# module_flags_reg.net
KiCad netlist of a schematic drawn in EAGLE
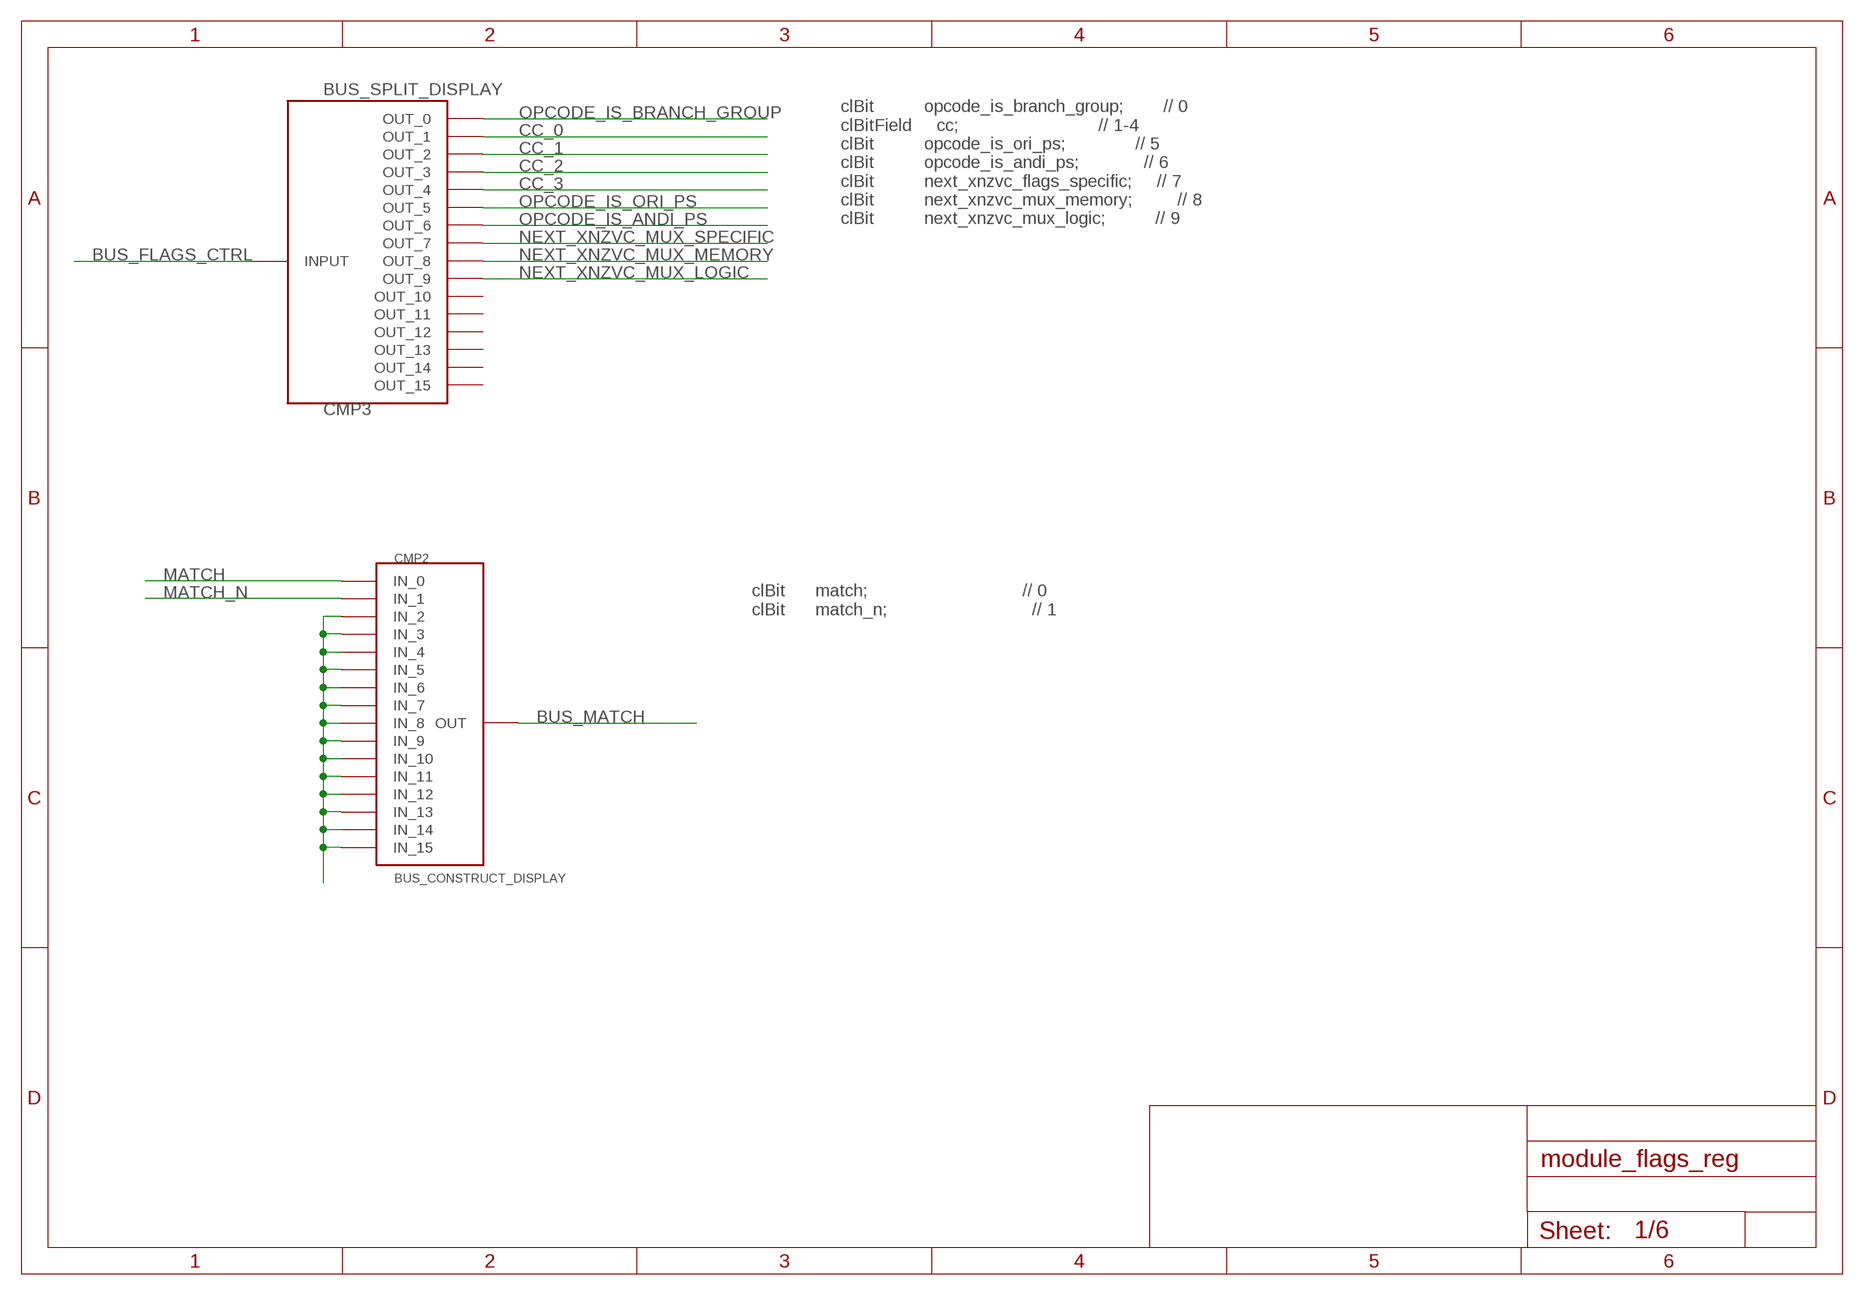
[diagram p0: schematic, sheet 1]
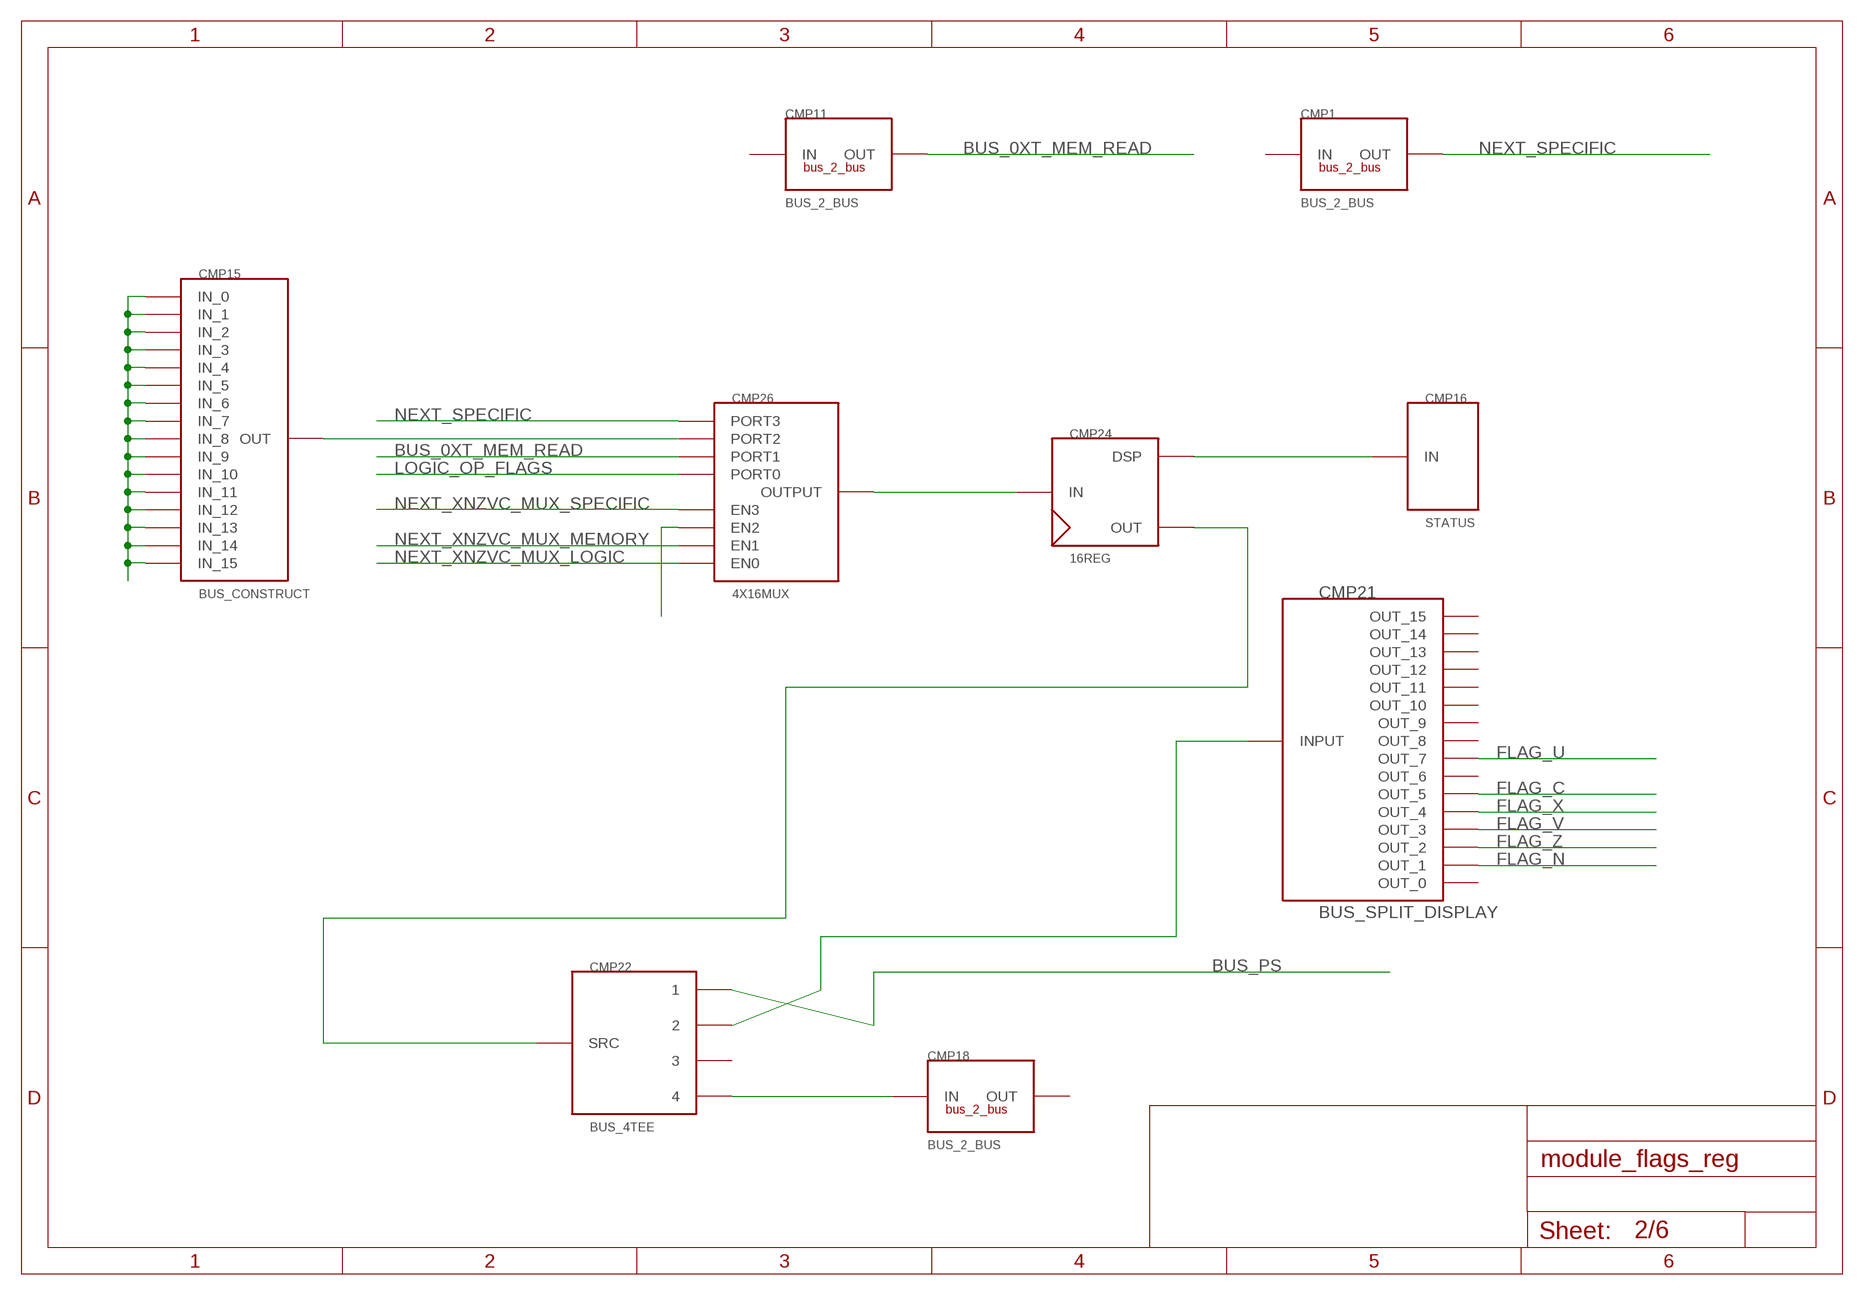
[diagram p1: schematic, sheet 2]
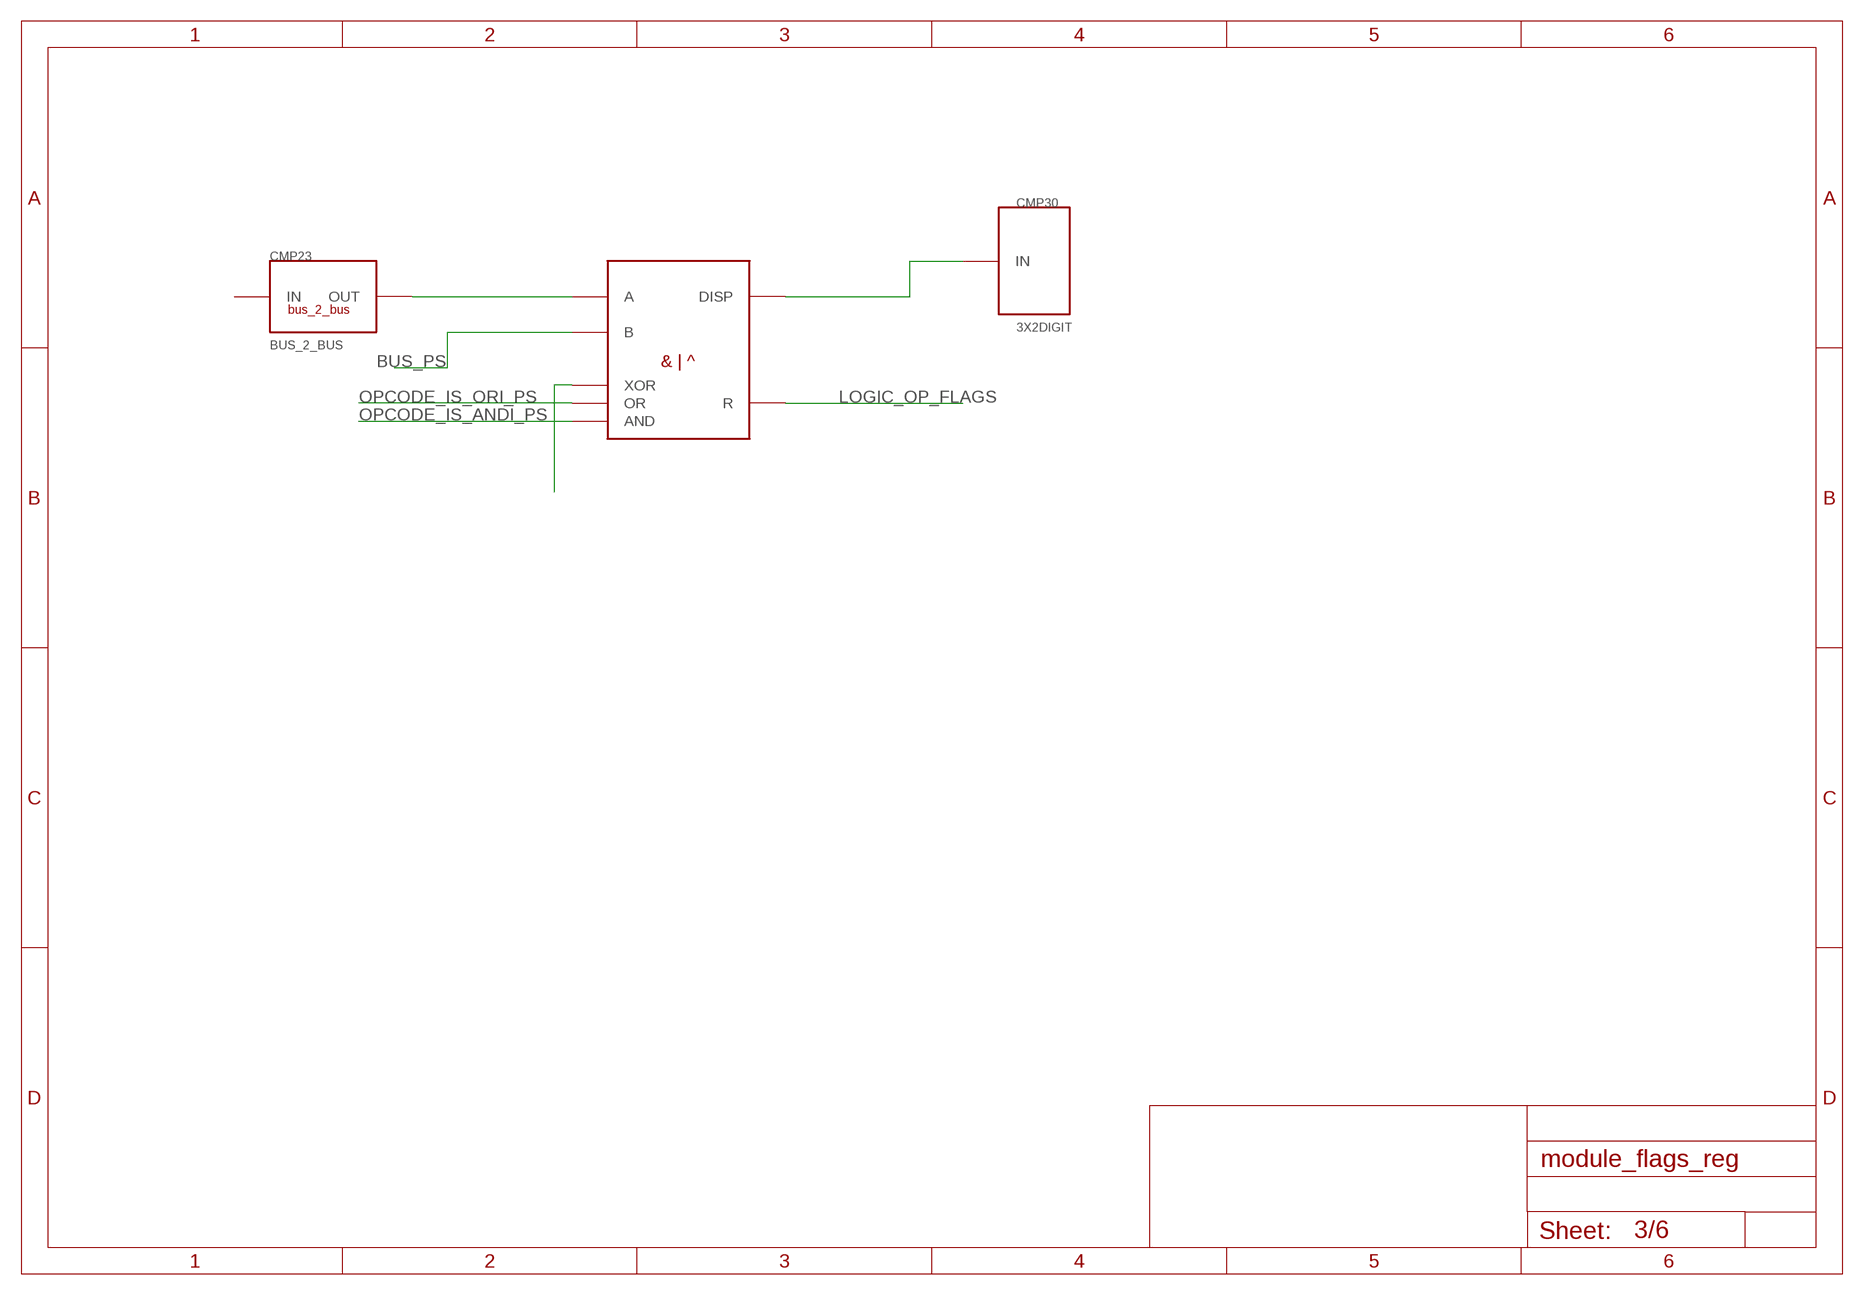
[diagram p2: schematic, sheet 3]
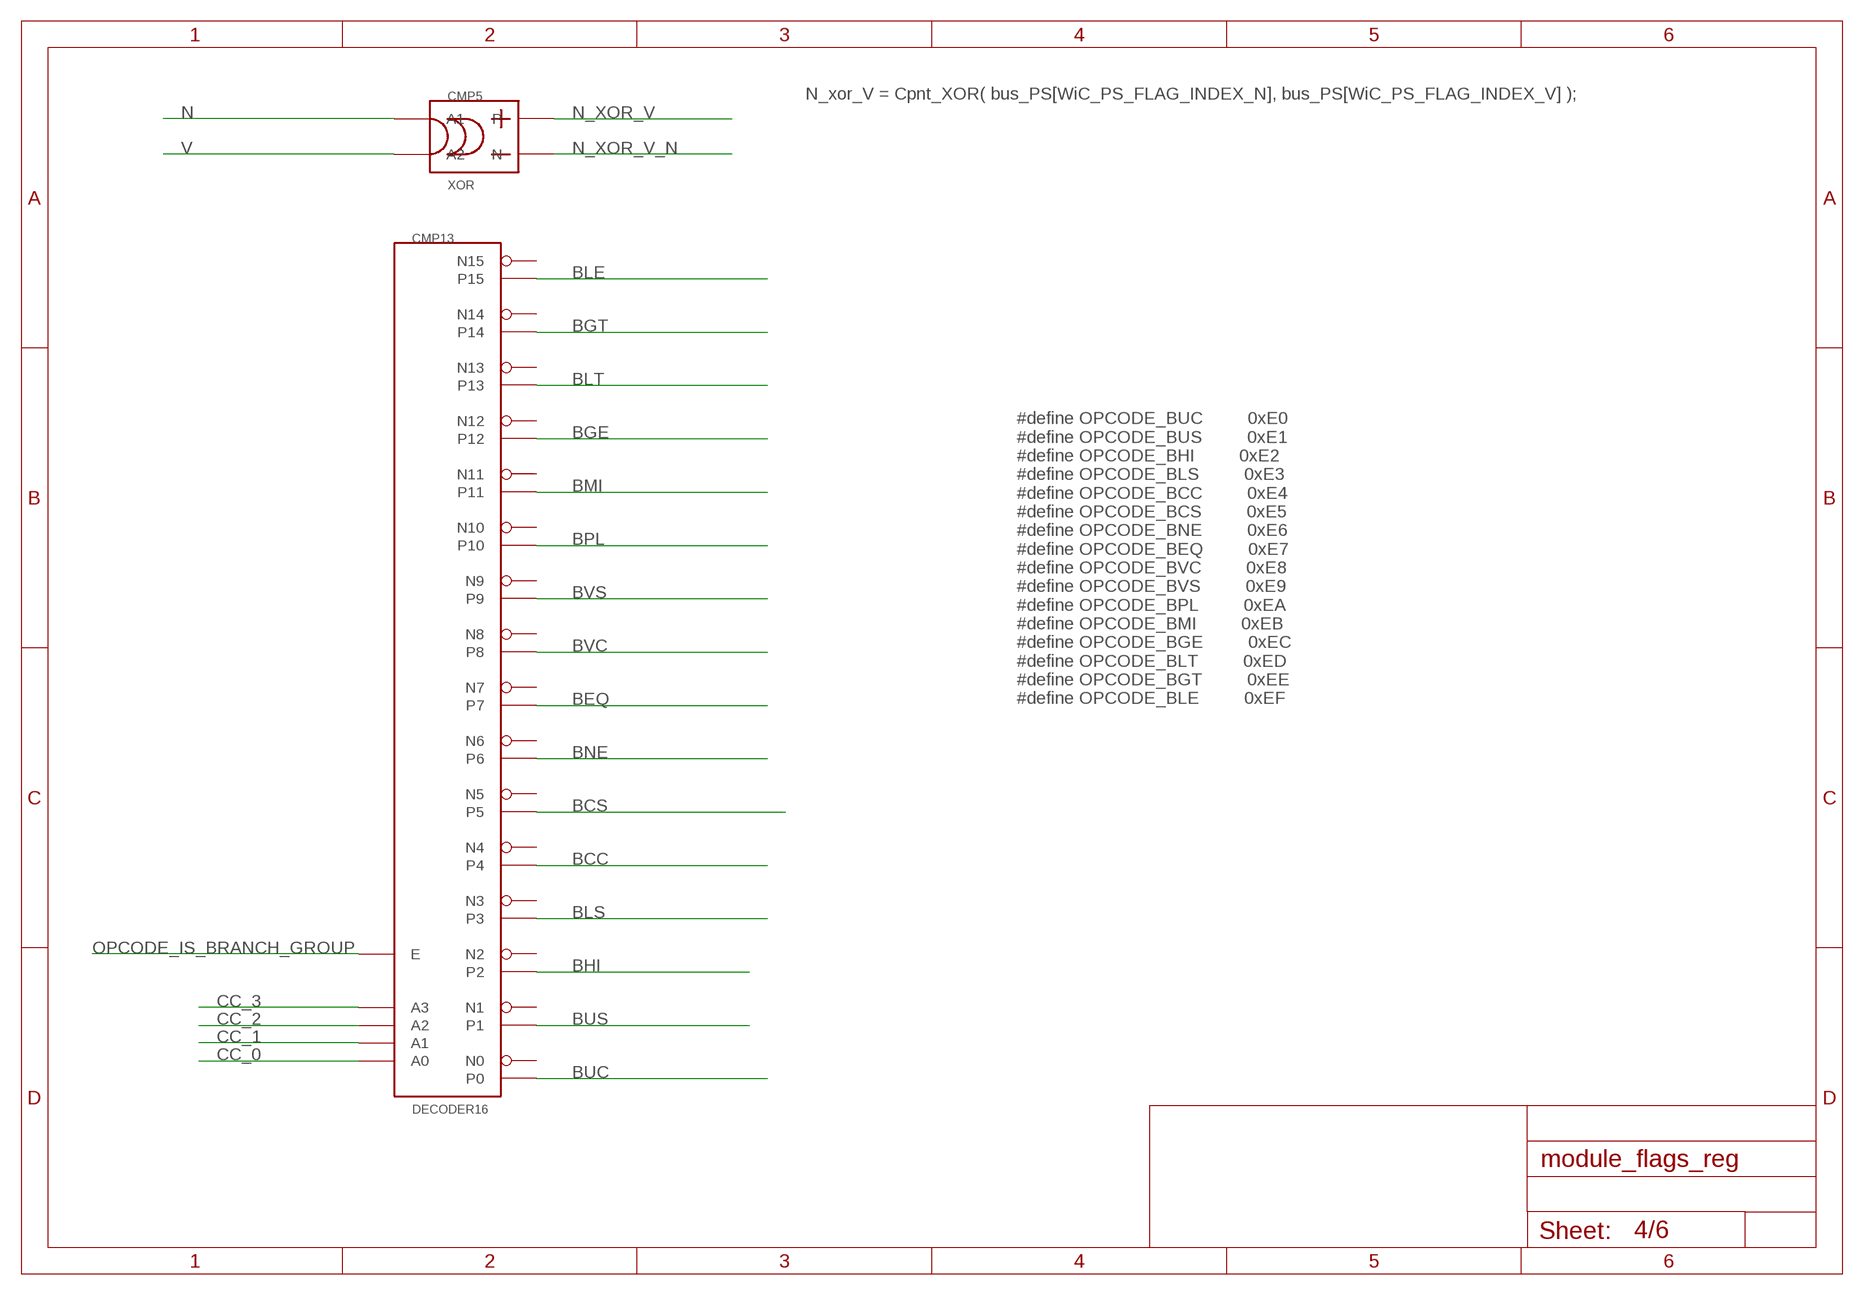
[diagram p3: schematic, sheet 4]
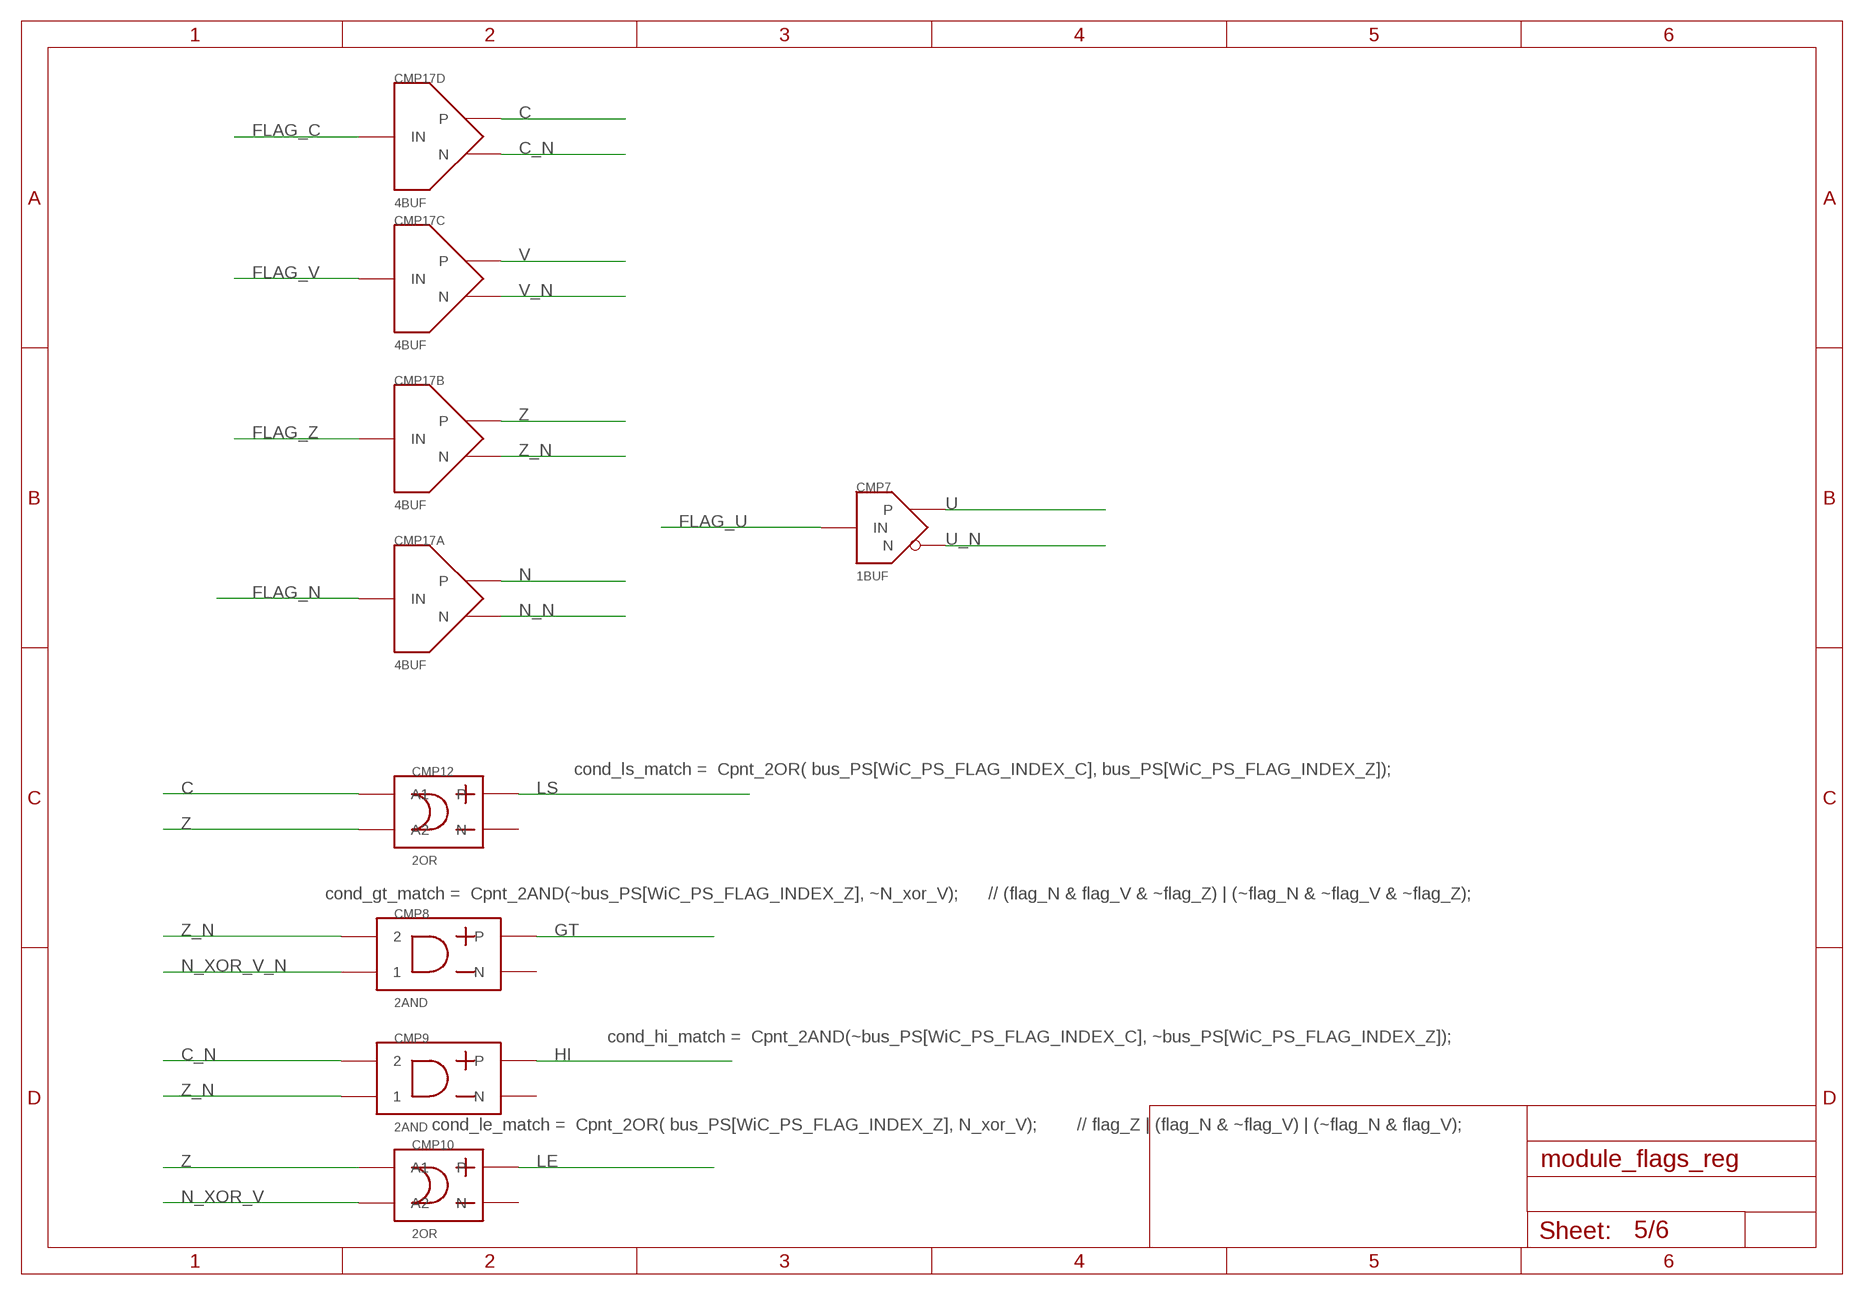
[diagram p4: schematic, sheet 5]
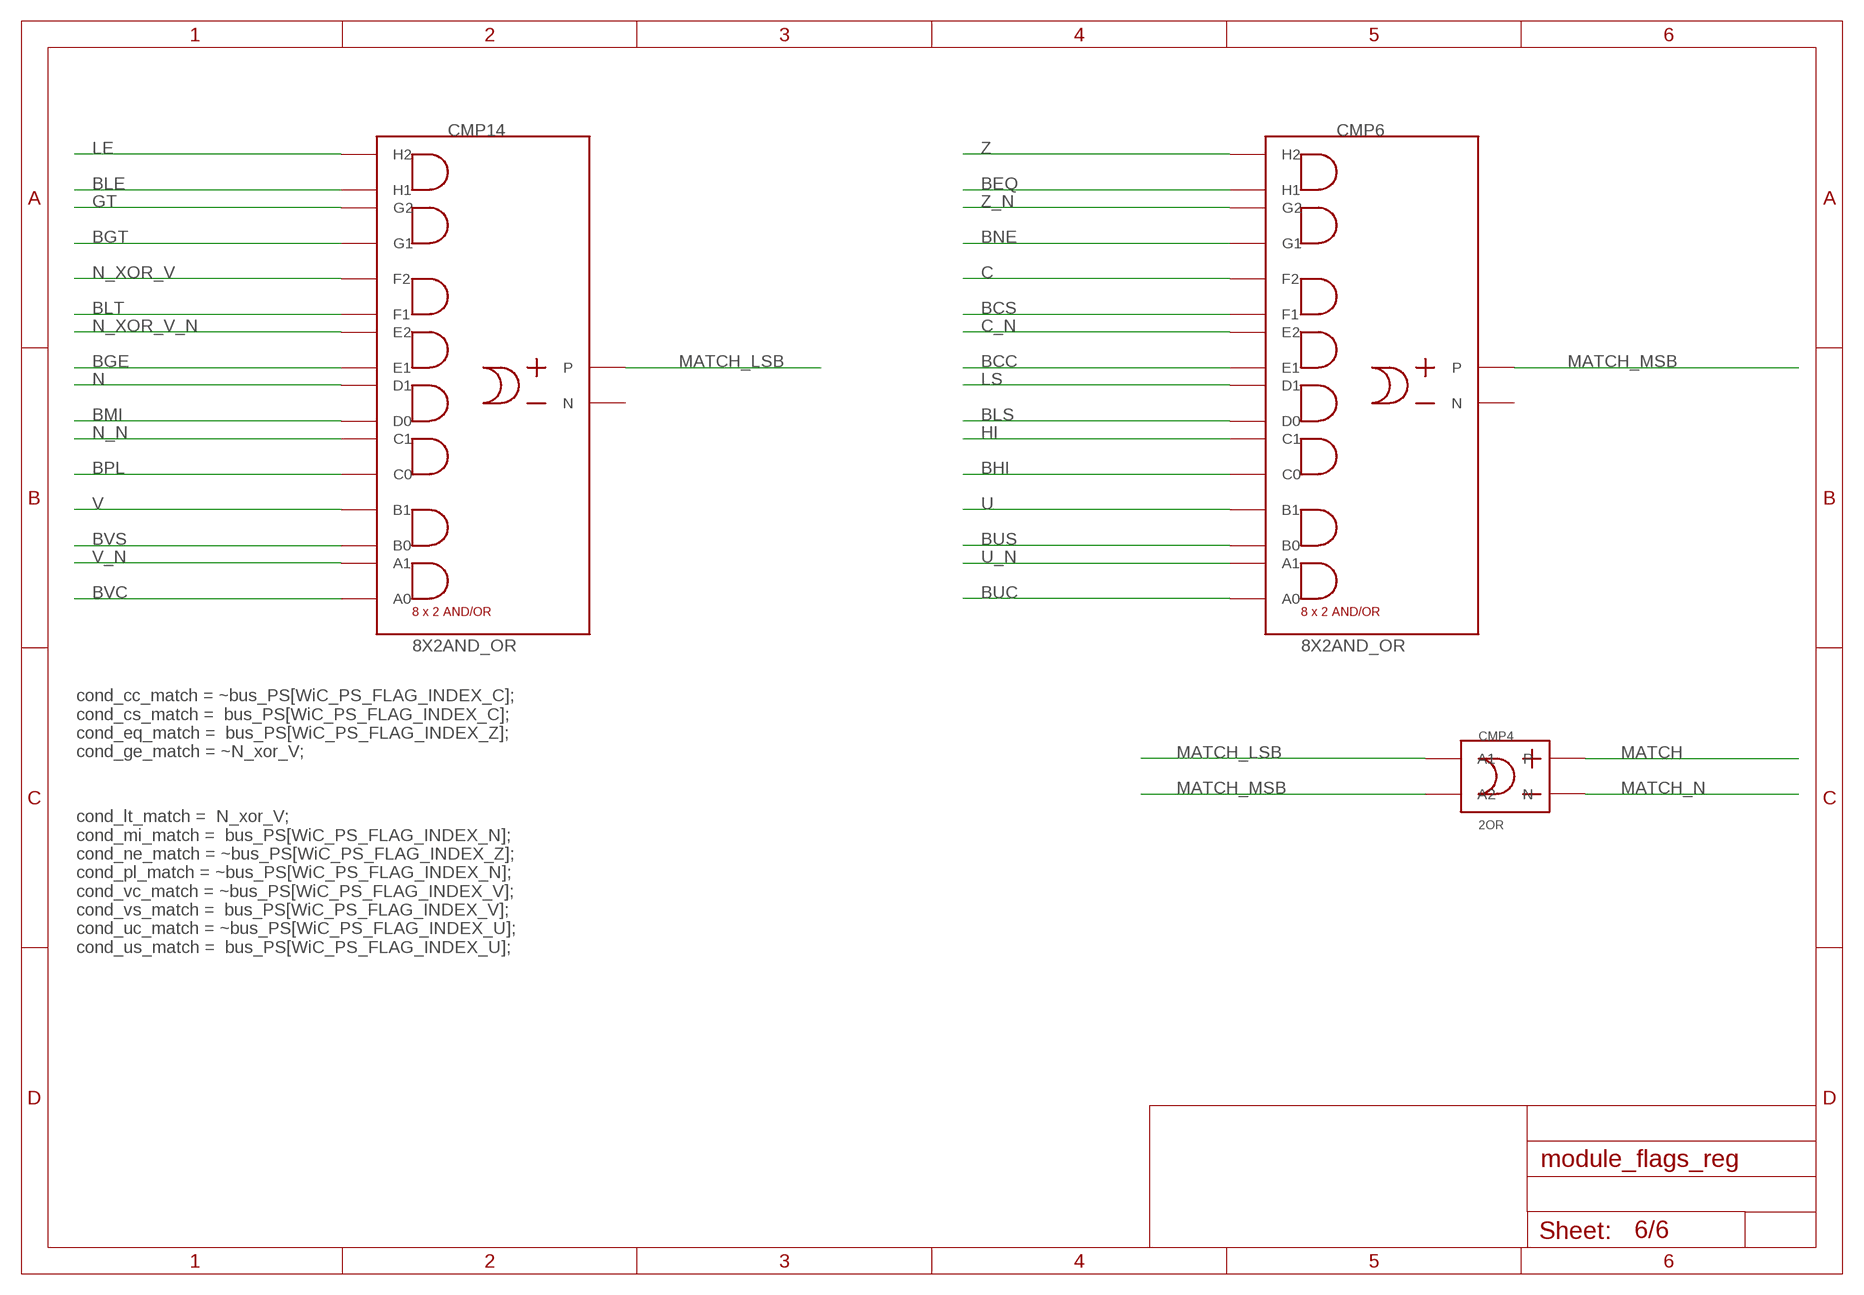
[diagram p5: schematic, sheet 6]

(export (version "E")
  (design (tool "Eeschema 10.0.6"))
  (components
    (comp (ref "CMP1")
      (value "BUS_2_BUS")
      (footprint "eagle-import:BUS2BUS")
      (libsource (lib "eagle-import") (part "BUS_2_BUS"))
    )
    (comp (ref "CMP11")
      (value "BUS_2_BUS")
      (footprint "eagle-import:BUS2BUS")
      (libsource (lib "eagle-import") (part "BUS_2_BUS"))
    )
    (comp (ref "CMP15")
      (value "BUS_CONSTRUCT")
      (footprint "eagle-import:BUS_SPLIT")
      (libsource (lib "eagle-import") (part "BUS_CONSTRUCT"))
    )
    (comp (ref "CMP16")
      (value "STATUS")
      (footprint "eagle-import:STATUS")
      (libsource (lib "eagle-import") (part "STATUS"))
    )
    (comp (ref "CMP18")
      (value "BUS_2_BUS")
      (footprint "eagle-import:BUS2BUS")
      (libsource (lib "eagle-import") (part "BUS_2_BUS"))
    )
    (comp (ref "CMP21")
      (value "BUS_SPLIT_DISPLAY")
      (footprint "eagle-import:BUS_SPLIT_DISPLAY")
      (libsource (lib "eagle-import") (part "BUS_SPLIT_DISPLAY"))
    )
    (comp (ref "CMP22")
      (value "BUS_4TEE")
      (footprint "eagle-import:BUS_4TEE")
      (libsource (lib "eagle-import") (part "BUS_4TEE"))
    )
    (comp (ref "CMP24")
      (value "16REG")
      (footprint "eagle-import:16REG")
      (libsource (lib "eagle-import") (part "16REG"))
    )
    (comp (ref "CMP26")
      (value "4X16MUX")
      (footprint "eagle-import:4X16MUX")
      (libsource (lib "eagle-import") (part "4X16MUX"))
    )
    (comp (ref "CMP4")
      (value "2OR")
      (footprint "eagle-import:2OR")
      (libsource (lib "eagle-import") (part "2OR"))
    )
    (comp (ref "CMP6")
      (value "8X2AND_OR")
      (footprint "eagle-import:8X2AND_OR")
      (libsource (lib "eagle-import") (part "8X2AND_OR"))
    )
    (comp (ref "CMP14")
      (value "8X2AND_OR")
      (footprint "eagle-import:8X2AND_OR")
      (libsource (lib "eagle-import") (part "8X2AND_OR"))
    )
    (comp (ref "CMP2")
      (value "BUS_CONSTRUCT_DISPLAY")
      (footprint "eagle-import:BUS_SPLIT_DISPLAY")
      (libsource (lib "eagle-import") (part "BUS_CONSTRUCT_DISPLAY"))
    )
    (comp (ref "CMP3")
      (value "BUS_SPLIT_DISPLAY")
      (footprint "eagle-import:BUS_SPLIT_DISPLAY")
      (libsource (lib "eagle-import") (part "BUS_SPLIT_DISPLAY"))
    )
    (comp (ref "CMP23")
      (value "BUS_2_BUS")
      (footprint "eagle-import:BUS2BUS")
      (libsource (lib "eagle-import") (part "BUS_2_BUS"))
    )
    (comp (ref "CMP28")
      (value "8BIT_LOGIC")
      (footprint "eagle-import:8BIT_LOGIC")
      (libsource (lib "eagle-import") (part "8BIT_LOGIC"))
    )
    (comp (ref "CMP30")
      (value "3X2DIGIT")
      (footprint "eagle-import:3X2DIGIT")
      (libsource (lib "eagle-import") (part "3X2DIGIT"))
    )
    (comp (ref "CMP7")
      (value "1BUF")
      (footprint "eagle-import:1BUF")
      (libsource (lib "eagle-import") (part "1BUF"))
    )
    (comp (ref "CMP8")
      (value "2AND")
      (footprint "eagle-import:2AND")
      (libsource (lib "eagle-import") (part "2AND"))
    )
    (comp (ref "CMP9")
      (value "2AND")
      (footprint "eagle-import:2AND")
      (libsource (lib "eagle-import") (part "2AND"))
    )
    (comp (ref "CMP10")
      (value "2OR")
      (footprint "eagle-import:2OR")
      (libsource (lib "eagle-import") (part "2OR"))
    )
    (comp (ref "CMP12")
      (value "2OR")
      (footprint "eagle-import:2OR")
      (libsource (lib "eagle-import") (part "2OR"))
    )
    (comp (ref "CMP17")
      (value "4BUF")
      (footprint "eagle-import:4BUF")
      (libsource (lib "eagle-import") (part "4BUF"))
    )
    (comp (ref "CMP5")
      (value "XOR")
      (footprint "eagle-import:XOR")
      (libsource (lib "eagle-import") (part "XOR"))
    )
    (comp (ref "CMP13")
      (value "DECODER16")
      (footprint "eagle-import:DECODER16")
      (libsource (lib "eagle-import") (part "DECODER16"))
    )
  )
  (nets
    (net (code "1") (name "BCC") (class "Default")
      (node (ref "CMP13") (pin "P4") (pinfunction "P4_P4") (pintype "output"))
      (node (ref "CMP6") (pin "P$9") (pinfunction "E1_P$9") (pintype "input"))
    )
    (net (code "2") (name "BCS") (class "Default")
      (node (ref "CMP13") (pin "P5") (pinfunction "P5_P5") (pintype "output"))
      (node (ref "CMP6") (pin "P$11") (pinfunction "F1_P$11") (pintype "input"))
    )
    (net (code "3") (name "BEQ") (class "Default")
      (node (ref "CMP13") (pin "P7") (pinfunction "P7_P7") (pintype "output"))
      (node (ref "CMP6") (pin "P$15") (pinfunction "H1_P$15") (pintype "input"))
    )
    (net (code "4") (name "BGE") (class "Default")
      (node (ref "CMP13") (pin "P12") (pinfunction "P12_P12") (pintype "output"))
      (node (ref "CMP14") (pin "P$9") (pinfunction "E1_P$9") (pintype "input"))
    )
    (net (code "5") (name "BGT") (class "Default")
      (node (ref "CMP13") (pin "P14") (pinfunction "P14_P14") (pintype "output"))
      (node (ref "CMP14") (pin "P$13") (pinfunction "G1_P$13") (pintype "input"))
    )
    (net (code "6") (name "BHI") (class "Default")
      (node (ref "CMP13") (pin "P2") (pinfunction "P2_P2") (pintype "output"))
      (node (ref "CMP6") (pin "P$5") (pinfunction "C0_P$5") (pintype "input"))
    )
    (net (code "7") (name "BLE") (class "Default")
      (node (ref "CMP13") (pin "P15") (pinfunction "P15_P15") (pintype "output"))
      (node (ref "CMP14") (pin "P$15") (pinfunction "H1_P$15") (pintype "input"))
    )
    (net (code "8") (name "BLS") (class "Default")
      (node (ref "CMP13") (pin "P3") (pinfunction "P3_P3") (pintype "output"))
      (node (ref "CMP6") (pin "P$7") (pinfunction "D0_P$7") (pintype "input"))
    )
    (net (code "9") (name "BLT") (class "Default")
      (node (ref "CMP13") (pin "P13") (pinfunction "P13_P13") (pintype "output"))
      (node (ref "CMP14") (pin "P$11") (pinfunction "F1_P$11") (pintype "input"))
    )
    (net (code "10") (name "BMI") (class "Default")
      (node (ref "CMP13") (pin "P11") (pinfunction "P11_P11") (pintype "output"))
      (node (ref "CMP14") (pin "P$7") (pinfunction "D0_P$7") (pintype "input"))
    )
    (net (code "11") (name "BNE") (class "Default")
      (node (ref "CMP13") (pin "P6") (pinfunction "P6_P6") (pintype "output"))
      (node (ref "CMP6") (pin "P$13") (pinfunction "G1_P$13") (pintype "input"))
    )
    (net (code "12") (name "BPL") (class "Default")
      (node (ref "CMP13") (pin "P10") (pinfunction "P10_P10") (pintype "output"))
      (node (ref "CMP14") (pin "P$5") (pinfunction "C0_P$5") (pintype "input"))
    )
    (net (code "13") (name "BUC") (class "Default")
      (node (ref "CMP13") (pin "P0") (pinfunction "P0_P0") (pintype "output"))
      (node (ref "CMP6") (pin "P$1") (pinfunction "A0_P$1") (pintype "input"))
    )
    (net (code "14") (name "BUS") (class "Default")
      (node (ref "CMP13") (pin "P1") (pinfunction "P1_P1") (pintype "output"))
      (node (ref "CMP6") (pin "P$3") (pinfunction "B0_P$3") (pintype "input"))
    )
    (net (code "15") (name "BUS_0XT_MEM_READ") (class "Default")
      (node (ref "CMP11") (pin "P$2") (pinfunction "OUT_P$2") (pintype "output"))
      (node (ref "CMP26") (pin "PORT1") (pinfunction "PORT1_PORT1") (pintype "input"))
    )
    (net (code "16") (name "BUS_FLAGS_CTRL") (class "Default")
      (node (ref "CMP3") (pin "INPUT") (pinfunction "INPUT_INPUT") (pintype "input"))
    )
    (net (code "17") (name "BUS_MATCH") (class "Default")
      (node (ref "CMP2") (pin "INPUT") (pinfunction "OUT_INPUT") (pintype "output"))
    )
    (net (code "18") (name "BUS_PS") (class "Default")
      (node (ref "CMP22") (pin "1") (pinfunction "1_1") (pintype "output"))
      (node (ref "CMP28") (pin "B") (pinfunction "B_B") (pintype "input"))
    )
    (net (code "19") (name "BVC") (class "Default")
      (node (ref "CMP13") (pin "P8") (pinfunction "P8_P8") (pintype "output"))
      (node (ref "CMP14") (pin "P$1") (pinfunction "A0_P$1") (pintype "input"))
    )
    (net (code "20") (name "BVS") (class "Default")
      (node (ref "CMP13") (pin "P9") (pinfunction "P9_P9") (pintype "output"))
      (node (ref "CMP14") (pin "P$3") (pinfunction "B0_P$3") (pintype "input"))
    )
    (net (code "21") (name "C") (class "Default")
      (node (ref "CMP12") (pin "P$2") (pinfunction "A1_P$2") (pintype "input"))
      (node (ref "CMP17") (pin "P4") (pinfunction "P_P4") (pintype "output"))
      (node (ref "CMP6") (pin "P$12") (pinfunction "F2_P$12") (pintype "input"))
    )
    (net (code "22") (name "CC_0") (class "Default")
      (node (ref "CMP13") (pin "A0") (pinfunction "A0_A0") (pintype "input"))
      (node (ref "CMP3") (pin "P$2") (pinfunction "OUT_1_P$2") (pintype "output"))
    )
    (net (code "23") (name "CC_1") (class "Default")
      (node (ref "CMP13") (pin "A1") (pinfunction "A1_A1") (pintype "input"))
      (node (ref "CMP3") (pin "P$3") (pinfunction "OUT_2_P$3") (pintype "output"))
    )
    (net (code "24") (name "CC_2") (class "Default")
      (node (ref "CMP13") (pin "A2") (pinfunction "A2_A2") (pintype "input"))
      (node (ref "CMP3") (pin "P$4") (pinfunction "OUT_3_P$4") (pintype "output"))
    )
    (net (code "25") (name "CC_3") (class "Default")
      (node (ref "CMP13") (pin "A3") (pinfunction "A3_A3") (pintype "input"))
      (node (ref "CMP3") (pin "P$5") (pinfunction "OUT_4_P$5") (pintype "output"))
    )
    (net (code "26") (name "C_N") (class "Default")
      (node (ref "CMP17") (pin "N4") (pinfunction "N_N4") (pintype "output"))
      (node (ref "CMP6") (pin "P$10") (pinfunction "E2_P$10") (pintype "input"))
      (node (ref "CMP9") (pin "P$2") (pinfunction "2_P$2") (pintype "input"))
    )
    (net (code "27") (name "FLAG_C") (class "Default")
      (node (ref "CMP17") (pin "A4") (pinfunction "IN_A4") (pintype "input"))
      (node (ref "CMP21") (pin "P$6") (pinfunction "OUT_5_P$6") (pintype "output"))
    )
    (net (code "28") (name "FLAG_N") (class "Default")
      (node (ref "CMP17") (pin "A1") (pinfunction "IN_A1") (pintype "input"))
      (node (ref "CMP21") (pin "P$2") (pinfunction "OUT_1_P$2") (pintype "output"))
    )
    (net (code "29") (name "FLAG_U") (class "Default")
      (node (ref "CMP21") (pin "P$8") (pinfunction "OUT_7_P$8") (pintype "output"))
      (node (ref "CMP7") (pin "IN") (pinfunction "IN_IN") (pintype "input"))
    )
    (net (code "30") (name "FLAG_V") (class "Default")
      (node (ref "CMP17") (pin "A3") (pinfunction "IN_A3") (pintype "input"))
      (node (ref "CMP21") (pin "P$4") (pinfunction "OUT_3_P$4") (pintype "output"))
    )
    (net (code "31") (name "FLAG_X") (class "Default")
      (node (ref "CMP21") (pin "P$5") (pinfunction "OUT_4_P$5") (pintype "output"))
    )
    (net (code "32") (name "FLAG_Z") (class "Default")
      (node (ref "CMP17") (pin "A2") (pinfunction "IN_A2") (pintype "input"))
      (node (ref "CMP21") (pin "P$3") (pinfunction "OUT_2_P$3") (pintype "output"))
    )
    (net (code "33") (name "GT") (class "Default")
      (node (ref "CMP14") (pin "P$14") (pinfunction "G2_P$14") (pintype "input"))
      (node (ref "CMP8") (pin "OUT_P") (pinfunction "P_OUT_P") (pintype "output"))
    )
    (net (code "34") (name "HI") (class "Default")
      (node (ref "CMP6") (pin "P$6") (pinfunction "C1_P$6") (pintype "input"))
      (node (ref "CMP9") (pin "OUT_P") (pinfunction "P_OUT_P") (pintype "output"))
    )
    (net (code "35") (name "LE") (class "Default")
      (node (ref "CMP10") (pin "OUT_P") (pinfunction "P_OUT_P") (pintype "output"))
      (node (ref "CMP14") (pin "P$16") (pinfunction "H2_P$16") (pintype "input"))
    )
    (net (code "36") (name "LOGIC_OP_FLAGS") (class "Default")
      (node (ref "CMP26") (pin "PORT0") (pinfunction "PORT0_PORT0") (pintype "input"))
      (node (ref "CMP28") (pin "R") (pinfunction "R_R") (pintype "output"))
    )
    (net (code "37") (name "LS") (class "Default")
      (node (ref "CMP12") (pin "OUT_P") (pinfunction "P_OUT_P") (pintype "output"))
      (node (ref "CMP6") (pin "P$8") (pinfunction "D1_P$8") (pintype "input"))
    )
    (net (code "38") (name "MATCH") (class "Default")
      (node (ref "CMP2") (pin "P$1") (pinfunction "IN_0_P$1") (pintype "input"))
      (node (ref "CMP4") (pin "OUT_P") (pinfunction "P_OUT_P") (pintype "output"))
    )
    (net (code "39") (name "MATCH_LSB") (class "Default")
      (node (ref "CMP14") (pin "OUT_P") (pinfunction "P_OUT_P") (pintype "output"))
      (node (ref "CMP4") (pin "P$2") (pinfunction "A1_P$2") (pintype "input"))
    )
    (net (code "40") (name "MATCH_MSB") (class "Default")
      (node (ref "CMP4") (pin "P$1") (pinfunction "A2_P$1") (pintype "input"))
      (node (ref "CMP6") (pin "OUT_P") (pinfunction "P_OUT_P") (pintype "output"))
    )
    (net (code "41") (name "MATCH_N") (class "Default")
      (node (ref "CMP2") (pin "P$2") (pinfunction "IN_1_P$2") (pintype "input"))
      (node (ref "CMP4") (pin "OUT_M") (pinfunction "N_OUT_M") (pintype "output"))
    )
    (net (code "42") (name "N") (class "Default")
      (node (ref "CMP14") (pin "P$8") (pinfunction "D1_P$8") (pintype "input"))
      (node (ref "CMP17") (pin "P1") (pinfunction "P_P1") (pintype "output"))
      (node (ref "CMP5") (pin "P$1") (pinfunction "A1_P$1") (pintype "input"))
    )
    (net (code "43") (name "NEXT_SPECIFIC") (class "Default")
      (node (ref "CMP1") (pin "P$2") (pinfunction "OUT_P$2") (pintype "output"))
      (node (ref "CMP26") (pin "PORT3") (pinfunction "PORT3_PORT3") (pintype "input"))
    )
    (net (code "44") (name "NEXT_XNZVC_MUX_LOGIC") (class "Default")
      (node (ref "CMP26") (pin "EN0") (pinfunction "EN0_EN0") (pintype "input"))
      (node (ref "CMP3") (pin "P$10") (pinfunction "OUT_9_P$10") (pintype "output"))
    )
    (net (code "45") (name "NEXT_XNZVC_MUX_MEMORY") (class "Default")
      (node (ref "CMP26") (pin "EN1") (pinfunction "EN1_EN1") (pintype "input"))
      (node (ref "CMP3") (pin "P$9") (pinfunction "OUT_8_P$9") (pintype "output"))
    )
    (net (code "46") (name "NEXT_XNZVC_MUX_SPECIFIC") (class "Default")
      (node (ref "CMP26") (pin "EN3") (pinfunction "EN3_EN3") (pintype "input"))
      (node (ref "CMP3") (pin "P$8") (pinfunction "OUT_7_P$8") (pintype "output"))
    )
    (net (code "47") (name "N_N") (class "Default")
      (node (ref "CMP14") (pin "P$6") (pinfunction "C1_P$6") (pintype "input"))
      (node (ref "CMP17") (pin "N1") (pinfunction "N_N1") (pintype "output"))
    )
    (net (code "48") (name "N_XOR_V") (class "Default")
      (node (ref "CMP10") (pin "P$1") (pinfunction "A2_P$1") (pintype "input"))
      (node (ref "CMP14") (pin "P$12") (pinfunction "F2_P$12") (pintype "input"))
      (node (ref "CMP5") (pin "OUT_P") (pinfunction "P_OUT_P") (pintype "output"))
    )
    (net (code "49") (name "N_XOR_V_N") (class "Default")
      (node (ref "CMP14") (pin "P$10") (pinfunction "E2_P$10") (pintype "input"))
      (node (ref "CMP5") (pin "OUT_N") (pinfunction "N_OUT_N") (pintype "output"))
      (node (ref "CMP8") (pin "P$1") (pinfunction "1_P$1") (pintype "input"))
    )
    (net (code "50") (name "Net-(CMP2-IN_10)") (class "Default")
      (node (ref "CMP2") (pin "P$10") (pinfunction "IN_9_P$10") (pintype "input"))
      (node (ref "CMP2") (pin "P$11") (pinfunction "IN_10_P$11") (pintype "input"))
      (node (ref "CMP2") (pin "P$12") (pinfunction "IN_11_P$12") (pintype "input"))
      (node (ref "CMP2") (pin "P$13") (pinfunction "IN_12_P$13") (pintype "input"))
      (node (ref "CMP2") (pin "P$14") (pinfunction "IN_13_P$14") (pintype "input"))
      (node (ref "CMP2") (pin "P$15") (pinfunction "IN_14_P$15") (pintype "input"))
      (node (ref "CMP2") (pin "P$16") (pinfunction "IN_15_P$16") (pintype "input"))
      (node (ref "CMP2") (pin "P$3") (pinfunction "IN_2_P$3") (pintype "input"))
      (node (ref "CMP2") (pin "P$4") (pinfunction "IN_3_P$4") (pintype "input"))
      (node (ref "CMP2") (pin "P$5") (pinfunction "IN_4_P$5") (pintype "input"))
      (node (ref "CMP2") (pin "P$6") (pinfunction "IN_5_P$6") (pintype "input"))
      (node (ref "CMP2") (pin "P$7") (pinfunction "IN_6_P$7") (pintype "input"))
      (node (ref "CMP2") (pin "P$8") (pinfunction "IN_7_P$8") (pintype "input"))
      (node (ref "CMP2") (pin "P$9") (pinfunction "IN_8_P$9") (pintype "input"))
    )
    (net (code "51") (name "Net-(CMP15-IN_0)") (class "Default")
      (node (ref "CMP15") (pin "P$1") (pinfunction "IN_0_P$1") (pintype "input"))
      (node (ref "CMP15") (pin "P$10") (pinfunction "IN_9_P$10") (pintype "input"))
      (node (ref "CMP15") (pin "P$11") (pinfunction "IN_10_P$11") (pintype "input"))
      (node (ref "CMP15") (pin "P$12") (pinfunction "IN_11_P$12") (pintype "input"))
      (node (ref "CMP15") (pin "P$13") (pinfunction "IN_12_P$13") (pintype "input"))
      (node (ref "CMP15") (pin "P$14") (pinfunction "IN_13_P$14") (pintype "input"))
      (node (ref "CMP15") (pin "P$15") (pinfunction "IN_14_P$15") (pintype "input"))
      (node (ref "CMP15") (pin "P$16") (pinfunction "IN_15_P$16") (pintype "input"))
      (node (ref "CMP15") (pin "P$2") (pinfunction "IN_1_P$2") (pintype "input"))
      (node (ref "CMP15") (pin "P$3") (pinfunction "IN_2_P$3") (pintype "input"))
      (node (ref "CMP15") (pin "P$4") (pinfunction "IN_3_P$4") (pintype "input"))
      (node (ref "CMP15") (pin "P$5") (pinfunction "IN_4_P$5") (pintype "input"))
      (node (ref "CMP15") (pin "P$6") (pinfunction "IN_5_P$6") (pintype "input"))
      (node (ref "CMP15") (pin "P$7") (pinfunction "IN_6_P$7") (pintype "input"))
      (node (ref "CMP15") (pin "P$8") (pinfunction "IN_7_P$8") (pintype "input"))
      (node (ref "CMP15") (pin "P$9") (pinfunction "IN_8_P$9") (pintype "input"))
    )
    (net (code "52") (name "Net-(CMP15-OUT)") (class "Default")
      (node (ref "CMP15") (pin "INPUT") (pinfunction "OUT_INPUT") (pintype "output"))
      (node (ref "CMP26") (pin "PORT2") (pinfunction "PORT2_PORT2") (pintype "input"))
    )
    (net (code "53") (name "Net-(CMP16-IN)") (class "Default")
      (node (ref "CMP16") (pin "P$1") (pinfunction "IN_P$1") (pintype "input"))
      (node (ref "CMP24") (pin "DISPLAY") (pinfunction "DSP_DISPLAY") (pintype "output"))
    )
    (net (code "54") (name "Net-(CMP18-IN)") (class "Default")
      (node (ref "CMP18") (pin "P$1") (pinfunction "IN_P$1") (pintype "input"))
      (node (ref "CMP22") (pin "4") (pinfunction "4_4") (pintype "output"))
    )
    (net (code "55") (name "Net-(CMP21-PadINPUT)") (class "Default")
      (node (ref "CMP21") (pin "INPUT") (pinfunction "INPUT_INPUT") (pintype "input"))
      (node (ref "CMP22") (pin "2") (pinfunction "2_2") (pintype "output"))
    )
    (net (code "56") (name "Net-(CMP22-PadSRC)") (class "Default")
      (node (ref "CMP22") (pin "SRC") (pinfunction "SRC_SRC") (pintype "input"))
      (node (ref "CMP24") (pin "OUT") (pinfunction "OUT_OUT") (pintype "output"))
    )
    (net (code "57") (name "Net-(CMP23-OUT)") (class "Default")
      (node (ref "CMP23") (pin "P$2") (pinfunction "OUT_P$2") (pintype "output"))
      (node (ref "CMP28") (pin "A") (pinfunction "A_A") (pintype "input"))
    )
    (net (code "58") (name "Net-(CMP24-IN)") (class "Default")
      (node (ref "CMP24") (pin "INPUT") (pinfunction "IN_INPUT") (pintype "input"))
      (node (ref "CMP26") (pin "PORTOUT") (pinfunction "OUTPUT_PORTOUT") (pintype "output"))
    )
    (net (code "59") (name "Net-(CMP30-IN)") (class "Default")
      (node (ref "CMP28") (pin "DISP") (pinfunction "DISP_DISP") (pintype "output"))
      (node (ref "CMP30") (pin "P$1") (pinfunction "IN_P$1") (pintype "input"))
    )
    (net (code "60") (name "OPCODE_IS_ANDI_PS") (class "Default")
      (node (ref "CMP28") (pin "AND") (pinfunction "AND_AND") (pintype "input"))
      (node (ref "CMP3") (pin "P$7") (pinfunction "OUT_6_P$7") (pintype "output"))
    )
    (net (code "61") (name "OPCODE_IS_BRANCH_GROUP") (class "Default")
      (node (ref "CMP13") (pin "E") (pinfunction "E_E") (pintype "input"))
      (node (ref "CMP3") (pin "P$1") (pinfunction "OUT_0_P$1") (pintype "output"))
    )
    (net (code "62") (name "OPCODE_IS_ORI_PS") (class "Default")
      (node (ref "CMP28") (pin "OR") (pinfunction "OR_OR") (pintype "input"))
      (node (ref "CMP3") (pin "P$6") (pinfunction "OUT_5_P$6") (pintype "output"))
    )
    (net (code "63") (name "U") (class "Default")
      (node (ref "CMP6") (pin "P$4") (pinfunction "B1_P$4") (pintype "input"))
      (node (ref "CMP7") (pin "P") (pinfunction "P_P") (pintype "output"))
    )
    (net (code "64") (name "U_N") (class "Default")
      (node (ref "CMP6") (pin "P$2") (pinfunction "A1_P$2") (pintype "input"))
      (node (ref "CMP7") (pin "N") (pinfunction "N_N") (pintype "output"))
    )
    (net (code "65") (name "V") (class "Default")
      (node (ref "CMP14") (pin "P$4") (pinfunction "B1_P$4") (pintype "input"))
      (node (ref "CMP17") (pin "P3") (pinfunction "P_P3") (pintype "output"))
      (node (ref "CMP5") (pin "P$2") (pinfunction "A2_P$2") (pintype "input"))
    )
    (net (code "66") (name "V_N") (class "Default")
      (node (ref "CMP14") (pin "P$2") (pinfunction "A1_P$2") (pintype "input"))
      (node (ref "CMP17") (pin "N3") (pinfunction "N_N3") (pintype "output"))
    )
    (net (code "67") (name "Z") (class "Default")
      (node (ref "CMP10") (pin "P$2") (pinfunction "A1_P$2") (pintype "input"))
      (node (ref "CMP12") (pin "P$1") (pinfunction "A2_P$1") (pintype "input"))
      (node (ref "CMP17") (pin "P2") (pinfunction "P_P2") (pintype "output"))
      (node (ref "CMP6") (pin "P$16") (pinfunction "H2_P$16") (pintype "input"))
    )
    (net (code "68") (name "Z_N") (class "Default")
      (node (ref "CMP17") (pin "N2") (pinfunction "N_N2") (pintype "output"))
      (node (ref "CMP6") (pin "P$14") (pinfunction "G2_P$14") (pintype "input"))
      (node (ref "CMP8") (pin "P$2") (pinfunction "2_P$2") (pintype "input"))
      (node (ref "CMP9") (pin "P$1") (pinfunction "1_P$1") (pintype "input"))
    )
    (net (code "69") (name "unconnected-(CMP1-IN-PadP$1)") (class "Default")
      (node (ref "CMP1") (pin "P$1") (pinfunction "IN_P$1") (pintype "input"))
    )
    (net (code "70") (name "unconnected-(CMP3-OUT_10-PadP$11)") (class "Default")
      (node (ref "CMP3") (pin "P$11") (pinfunction "OUT_10_P$11") (pintype "output"))
    )
    (net (code "71") (name "unconnected-(CMP3-OUT_11-PadP$12)") (class "Default")
      (node (ref "CMP3") (pin "P$12") (pinfunction "OUT_11_P$12") (pintype "output"))
    )
    (net (code "72") (name "unconnected-(CMP3-OUT_12-PadP$13)") (class "Default")
      (node (ref "CMP3") (pin "P$13") (pinfunction "OUT_12_P$13") (pintype "output"))
    )
    (net (code "73") (name "unconnected-(CMP3-OUT_13-PadP$14)") (class "Default")
      (node (ref "CMP3") (pin "P$14") (pinfunction "OUT_13_P$14") (pintype "output"))
    )
    (net (code "74") (name "unconnected-(CMP3-OUT_14-PadP$15)") (class "Default")
      (node (ref "CMP3") (pin "P$15") (pinfunction "OUT_14_P$15") (pintype "output"))
    )
    (net (code "75") (name "unconnected-(CMP3-OUT_15-PadP$16)") (class "Default")
      (node (ref "CMP3") (pin "P$16") (pinfunction "OUT_15_P$16") (pintype "output"))
    )
    (net (code "76") (name "unconnected-(CMP6-N-PadOUT_M)") (class "Default")
      (node (ref "CMP6") (pin "OUT_M") (pinfunction "N_OUT_M") (pintype "output"))
    )
    (net (code "77") (name "unconnected-(CMP8-N-PadOUT_M)") (class "Default")
      (node (ref "CMP8") (pin "OUT_M") (pinfunction "N_OUT_M") (pintype "output"))
    )
    (net (code "78") (name "unconnected-(CMP9-N-PadOUT_M)") (class "Default")
      (node (ref "CMP9") (pin "OUT_M") (pinfunction "N_OUT_M") (pintype "output"))
    )
    (net (code "79") (name "unconnected-(CMP10-N-PadOUT_M)") (class "Default")
      (node (ref "CMP10") (pin "OUT_M") (pinfunction "N_OUT_M") (pintype "output"))
    )
    (net (code "80") (name "unconnected-(CMP11-IN-PadP$1)") (class "Default")
      (node (ref "CMP11") (pin "P$1") (pinfunction "IN_P$1") (pintype "input"))
    )
    (net (code "81") (name "unconnected-(CMP12-N-PadOUT_M)") (class "Default")
      (node (ref "CMP12") (pin "OUT_M") (pinfunction "N_OUT_M") (pintype "output"))
    )
    (net (code "82") (name "unconnected-(CMP13-PadN0)") (class "Default")
      (node (ref "CMP13") (pin "N0") (pinfunction "N0_N0") (pintype "output"))
    )
    (net (code "83") (name "unconnected-(CMP13-PadN1)") (class "Default")
      (node (ref "CMP13") (pin "N1") (pinfunction "N1_N1") (pintype "output"))
    )
    (net (code "84") (name "unconnected-(CMP13-PadN2)") (class "Default")
      (node (ref "CMP13") (pin "N2") (pinfunction "N2_N2") (pintype "output"))
    )
    (net (code "85") (name "unconnected-(CMP13-PadN3)") (class "Default")
      (node (ref "CMP13") (pin "N3") (pinfunction "N3_N3") (pintype "output"))
    )
    (net (code "86") (name "unconnected-(CMP13-PadN4)") (class "Default")
      (node (ref "CMP13") (pin "N4") (pinfunction "N4_N4") (pintype "output"))
    )
    (net (code "87") (name "unconnected-(CMP13-PadN5)") (class "Default")
      (node (ref "CMP13") (pin "N5") (pinfunction "N5_N5") (pintype "output"))
    )
    (net (code "88") (name "unconnected-(CMP13-PadN6)") (class "Default")
      (node (ref "CMP13") (pin "N6") (pinfunction "N6_N6") (pintype "output"))
    )
    (net (code "89") (name "unconnected-(CMP13-PadN7)") (class "Default")
      (node (ref "CMP13") (pin "N7") (pinfunction "N7_N7") (pintype "output"))
    )
    (net (code "90") (name "unconnected-(CMP13-PadN8)") (class "Default")
      (node (ref "CMP13") (pin "N8") (pinfunction "N8_N8") (pintype "output"))
    )
    (net (code "91") (name "unconnected-(CMP13-PadN9)") (class "Default")
      (node (ref "CMP13") (pin "N9") (pinfunction "N9_N9") (pintype "output"))
    )
    (net (code "92") (name "unconnected-(CMP13-PadN10)") (class "Default")
      (node (ref "CMP13") (pin "N10") (pinfunction "N10_N10") (pintype "output"))
    )
    (net (code "93") (name "unconnected-(CMP13-PadN11)") (class "Default")
      (node (ref "CMP13") (pin "N11") (pinfunction "N11_N11") (pintype "output"))
    )
    (net (code "94") (name "unconnected-(CMP13-PadN12)") (class "Default")
      (node (ref "CMP13") (pin "N12") (pinfunction "N12_N12") (pintype "output"))
    )
    (net (code "95") (name "unconnected-(CMP13-PadN13)") (class "Default")
      (node (ref "CMP13") (pin "N13") (pinfunction "N13_N13") (pintype "output"))
    )
    (net (code "96") (name "unconnected-(CMP13-PadN14)") (class "Default")
      (node (ref "CMP13") (pin "N14") (pinfunction "N14_N14") (pintype "output"))
    )
    (net (code "97") (name "unconnected-(CMP13-PadN15)") (class "Default")
      (node (ref "CMP13") (pin "N15") (pinfunction "N15_N15") (pintype "output"))
    )
    (net (code "98") (name "unconnected-(CMP14-N-PadOUT_M)") (class "Default")
      (node (ref "CMP14") (pin "OUT_M") (pinfunction "N_OUT_M") (pintype "output"))
    )
    (net (code "99") (name "unconnected-(CMP18-OUT-PadP$2)") (class "Default")
      (node (ref "CMP18") (pin "P$2") (pinfunction "OUT_P$2") (pintype "output"))
    )
    (net (code "100") (name "unconnected-(CMP21-OUT_0-PadP$1)") (class "Default")
      (node (ref "CMP21") (pin "P$1") (pinfunction "OUT_0_P$1") (pintype "output"))
    )
    (net (code "101") (name "unconnected-(CMP21-OUT_6-PadP$7)") (class "Default")
      (node (ref "CMP21") (pin "P$7") (pinfunction "OUT_6_P$7") (pintype "output"))
    )
    (net (code "102") (name "unconnected-(CMP21-OUT_8-PadP$9)") (class "Default")
      (node (ref "CMP21") (pin "P$9") (pinfunction "OUT_8_P$9") (pintype "output"))
    )
    (net (code "103") (name "unconnected-(CMP21-OUT_9-PadP$10)") (class "Default")
      (node (ref "CMP21") (pin "P$10") (pinfunction "OUT_9_P$10") (pintype "output"))
    )
    (net (code "104") (name "unconnected-(CMP21-OUT_10-PadP$11)") (class "Default")
      (node (ref "CMP21") (pin "P$11") (pinfunction "OUT_10_P$11") (pintype "output"))
    )
    (net (code "105") (name "unconnected-(CMP21-OUT_11-PadP$12)") (class "Default")
      (node (ref "CMP21") (pin "P$12") (pinfunction "OUT_11_P$12") (pintype "output"))
    )
    (net (code "106") (name "unconnected-(CMP21-OUT_12-PadP$13)") (class "Default")
      (node (ref "CMP21") (pin "P$13") (pinfunction "OUT_12_P$13") (pintype "output"))
    )
    (net (code "107") (name "unconnected-(CMP21-OUT_13-PadP$14)") (class "Default")
      (node (ref "CMP21") (pin "P$14") (pinfunction "OUT_13_P$14") (pintype "output"))
    )
    (net (code "108") (name "unconnected-(CMP21-OUT_14-PadP$15)") (class "Default")
      (node (ref "CMP21") (pin "P$15") (pinfunction "OUT_14_P$15") (pintype "output"))
    )
    (net (code "109") (name "unconnected-(CMP21-OUT_15-PadP$16)") (class "Default")
      (node (ref "CMP21") (pin "P$16") (pinfunction "OUT_15_P$16") (pintype "output"))
    )
    (net (code "110") (name "unconnected-(CMP22-Pad3)") (class "Default")
      (node (ref "CMP22") (pin "3") (pinfunction "3_3") (pintype "output"))
    )
    (net (code "111") (name "unconnected-(CMP23-IN-PadP$1)") (class "Default")
      (node (ref "CMP23") (pin "P$1") (pinfunction "IN_P$1") (pintype "input"))
    )
    (net (code "112") (name "unconnected-(CMP26-PadEN2)") (class "Default")
      (node (ref "CMP26") (pin "EN2") (pinfunction "EN2_EN2") (pintype "input"))
    )
    (net (code "113") (name "unconnected-(CMP28-PadXOR)") (class "Default")
      (node (ref "CMP28") (pin "XOR") (pinfunction "XOR_XOR") (pintype "input"))
    )
  )
)
